# CircuitPython_Macro_Keyboard.net
KiCad netlist of a schematic drawn in EasyEDA
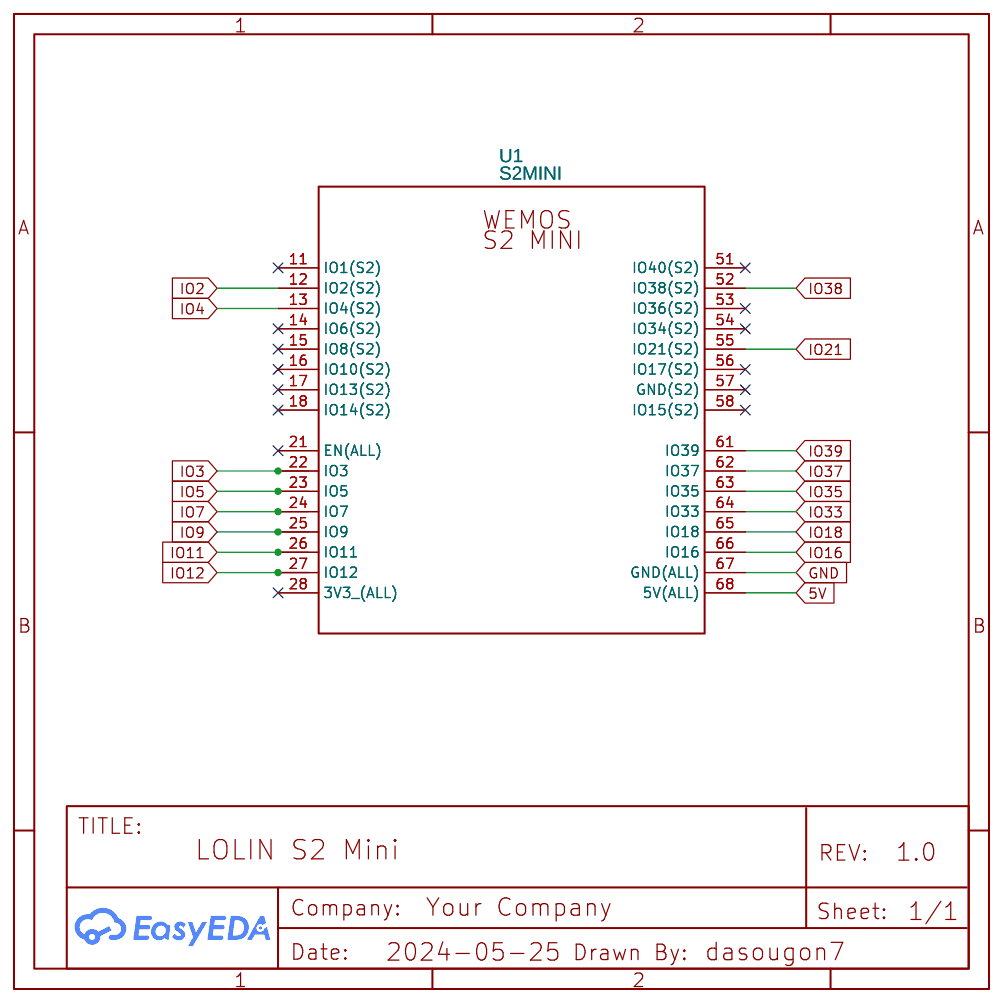
[diagram p0: LOLIN S2]
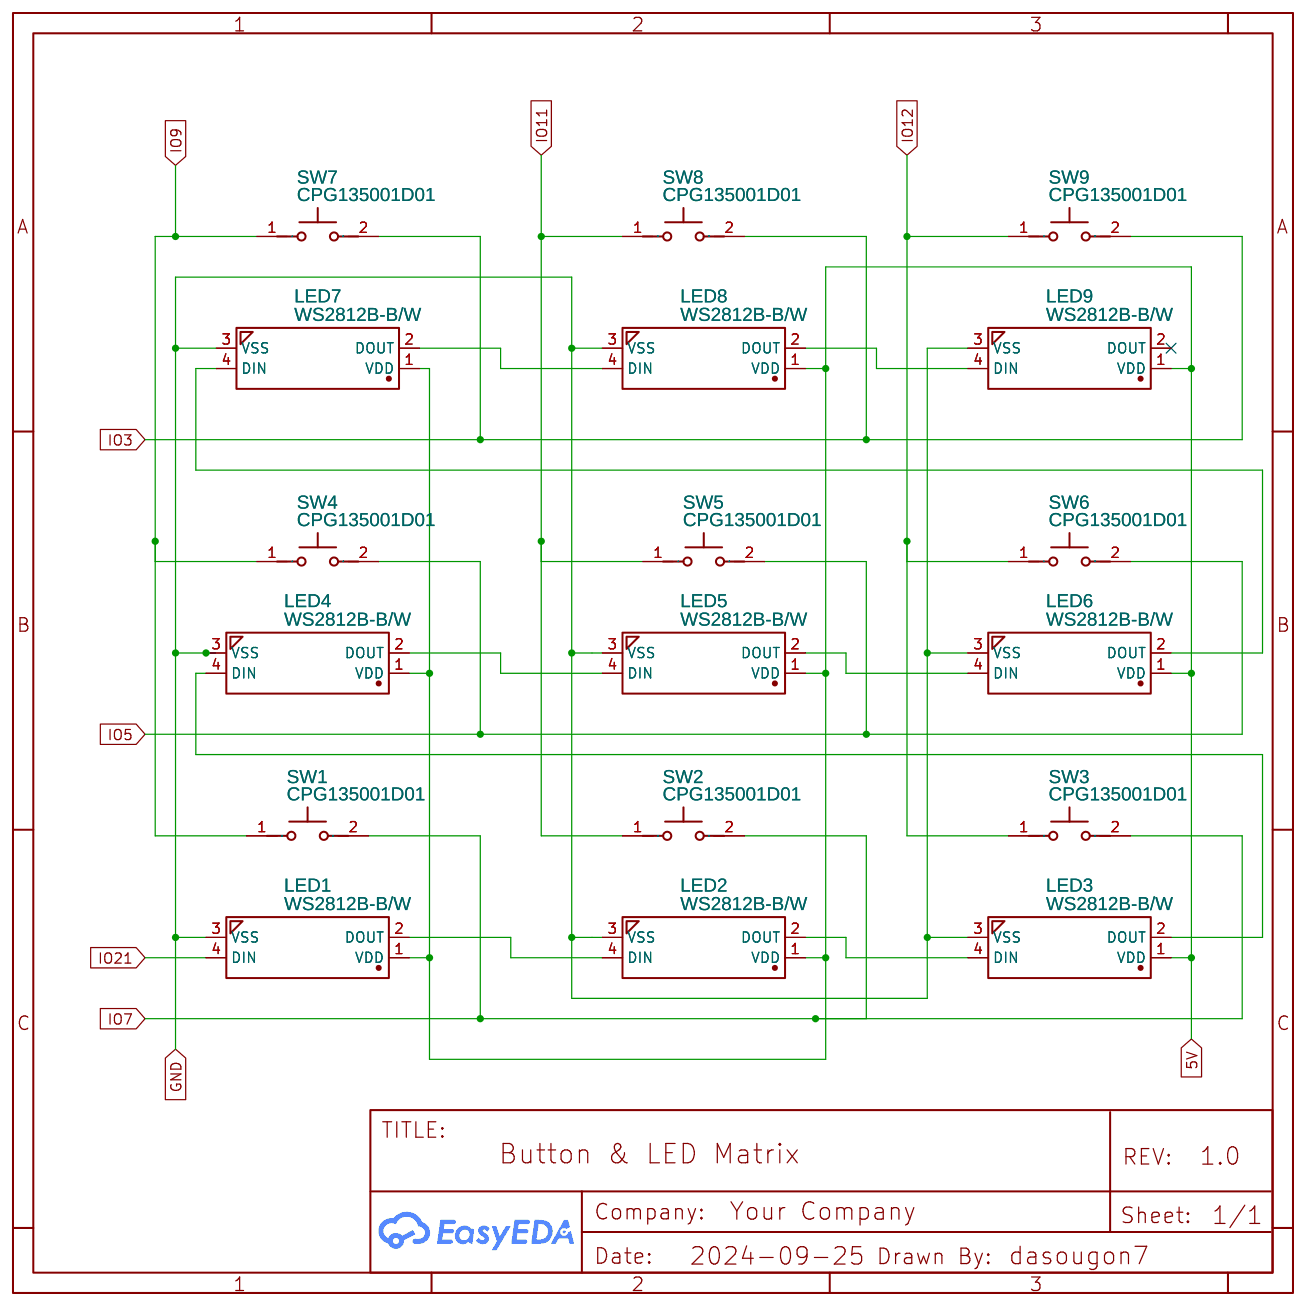
[diagram p1: Button Matrix]
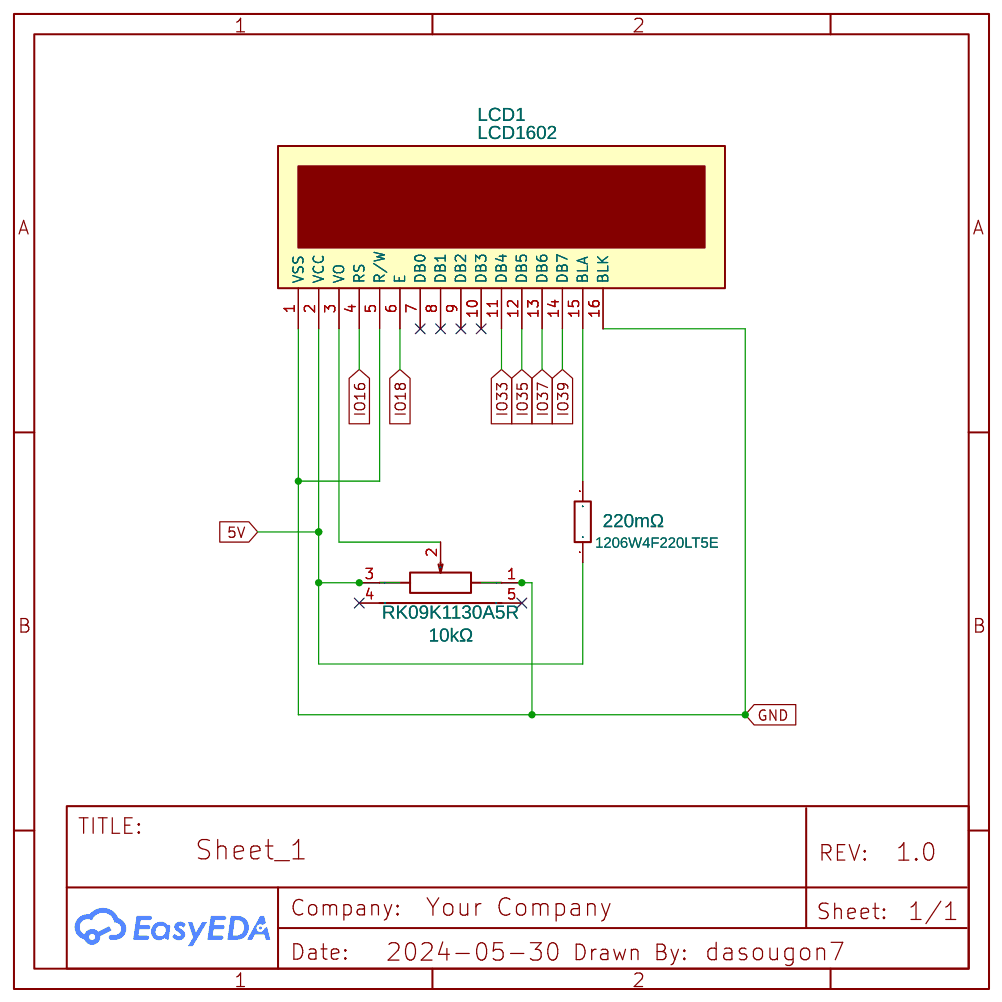
[diagram p2: LCD1602]
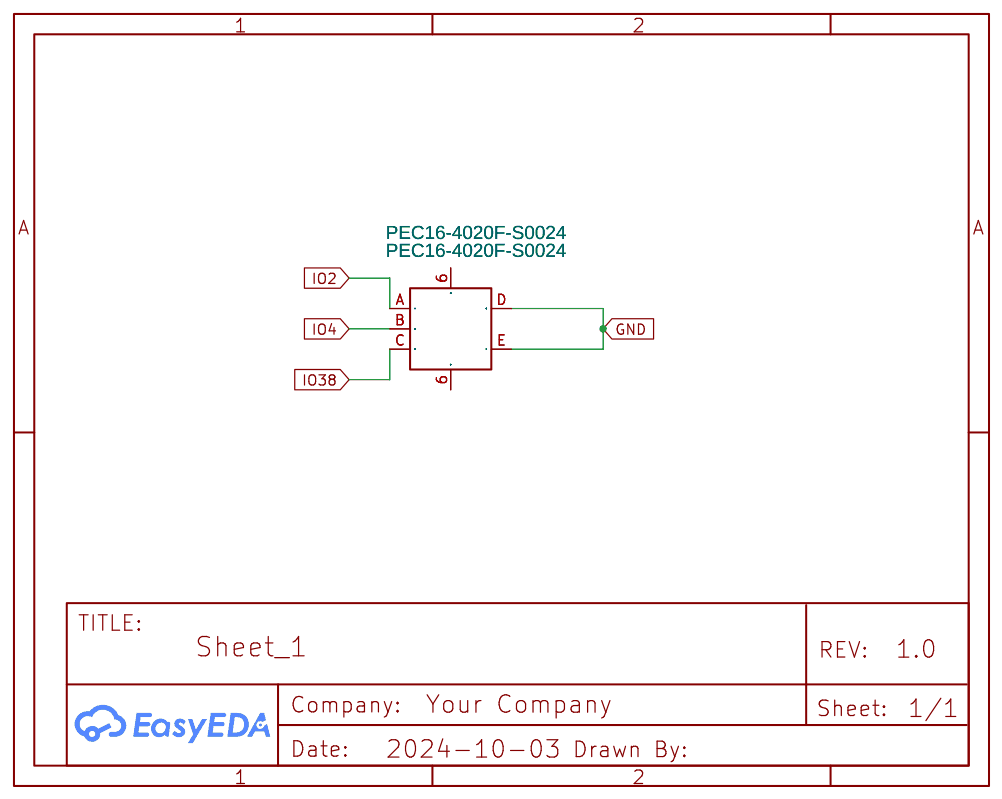
[diagram p3: Rotary Encoder]

(export (version "E")
  (design (tool "Eeschema 10.0.6"))
  (components
    (comp (ref "U1")
      (value "S2MINI")
      (fields (field (name "Manufacturer Part") "Wemos") (field (name "Manufacturer") "WEMOS"))
      (libsource (lib "") (part "S2MINI"))
    )
    (comp (ref "LED1")
      (value "WS2812B-B/W")
      (fields (field (name "Manufacturer Part") "WS2812B-B/T") (field (name "Manufacturer") "worldsemi"))
      (libsource (lib "") (part "WS2812B-B/W"))
    )
    (comp (ref "LED2")
      (value "WS2812B-B/W")
      (fields (field (name "Manufacturer Part") "WS2812B-B/T") (field (name "Manufacturer") "worldsemi"))
      (libsource (lib "") (part "WS2812B-B/W"))
    )
    (comp (ref "LED3")
      (value "WS2812B-B/W")
      (fields (field (name "Manufacturer Part") "WS2812B-B/T") (field (name "Manufacturer") "worldsemi"))
      (libsource (lib "") (part "WS2812B-B/W"))
    )
    (comp (ref "LED4")
      (value "WS2812B-B/W")
      (fields (field (name "Manufacturer Part") "WS2812B-B/T") (field (name "Manufacturer") "worldsemi"))
      (libsource (lib "") (part "WS2812B-B/W"))
    )
    (comp (ref "LED5")
      (value "WS2812B-B/W")
      (fields (field (name "Manufacturer Part") "WS2812B-B/T") (field (name "Manufacturer") "worldsemi"))
      (libsource (lib "") (part "WS2812B-B/W"))
    )
    (comp (ref "LED6")
      (value "WS2812B-B/W")
      (fields (field (name "Manufacturer Part") "WS2812B-B/T") (field (name "Manufacturer") "worldsemi"))
      (libsource (lib "") (part "WS2812B-B/W"))
    )
    (comp (ref "LED7")
      (value "WS2812B-B/W")
      (fields (field (name "Manufacturer Part") "WS2812B-B/T") (field (name "Manufacturer") "worldsemi"))
      (libsource (lib "") (part "WS2812B-B/W"))
    )
    (comp (ref "LED8")
      (value "WS2812B-B/W")
      (fields (field (name "Manufacturer Part") "WS2812B-B/T") (field (name "Manufacturer") "worldsemi"))
      (libsource (lib "") (part "WS2812B-B/W"))
    )
    (comp (ref "LED9")
      (value "WS2812B-B/W")
      (fields (field (name "Manufacturer Part") "WS2812B-B/T") (field (name "Manufacturer") "worldsemi"))
      (libsource (lib "") (part "WS2812B-B/W"))
    )
    (comp (ref "SW1")
      (value "CPG135001D01")
      (fields (field (name "Manufacturer") "Kailh(凯华)"))
      (libsource (lib "") (part "CPG135001D01"))
    )
    (comp (ref "SW2")
      (value "CPG135001D01")
      (fields (field (name "Manufacturer") "Kailh(凯华)"))
      (libsource (lib "") (part "CPG135001D01"))
    )
    (comp (ref "SW3")
      (value "CPG135001D01")
      (fields (field (name "Manufacturer") "Kailh(凯华)"))
      (libsource (lib "") (part "CPG135001D01"))
    )
    (comp (ref "SW4")
      (value "CPG135001D01")
      (fields (field (name "Manufacturer") "Kailh(凯华)"))
      (libsource (lib "") (part "CPG135001D01"))
    )
    (comp (ref "SW5")
      (value "CPG135001D01")
      (fields (field (name "Manufacturer") "Kailh(凯华)"))
      (libsource (lib "") (part "CPG135001D01"))
    )
    (comp (ref "SW6")
      (value "CPG135001D01")
      (fields (field (name "Manufacturer") "Kailh(凯华)"))
      (libsource (lib "") (part "CPG135001D01"))
    )
    (comp (ref "SW7")
      (value "CPG135001D01")
      (fields (field (name "Manufacturer") "Kailh(凯华)"))
      (libsource (lib "") (part "CPG135001D01"))
    )
    (comp (ref "SW8")
      (value "CPG135001D01")
      (fields (field (name "Manufacturer") "Kailh(凯华)"))
      (libsource (lib "") (part "CPG135001D01"))
    )
    (comp (ref "SW9")
      (value "CPG135001D01")
      (fields (field (name "Manufacturer") "Kailh(凯华)"))
      (libsource (lib "") (part "CPG135001D01"))
    )
    (comp (ref "1206W4F220LT5E")
      (value "220mΩ")
      (fields
        (field (name "Manufacturer Part") "1206W4F220LT5E")
        (field (name "Manufacturer") "UNI-ROYAL(厚声)")
      )
      (libsource (lib "") (part "1206W4F220LT5E"))
    )
    (comp (ref "LCD1")
      (value "LCD1602")
      (fields (field (name "Manufacturer Part") "HS1602A-Y") (field (name "Manufacturer") "HS(汉昇)"))
      (libsource (lib "") (part "LCD1602"))
    )
    (comp (ref "RK09K1130A5R")
      (value "10kΩ")
      (fields
        (field (name "Manufacturer Part") "RK09K1130A5R")
        (field (name "Manufacturer") "ALPSALPINE(阿尔卑斯阿尔派)")
      )
      (libsource (lib "") (part "RK09K1130A5R"))
    )
    (comp (ref "PEC16-4020F-S0024")
      (value "PEC16-4020F-S0024")
      (fields (field (name "Manufacturer") "BOURNS"))
      (libsource (lib "") (part "PEC16-4020F-S0024"))
    )
  )
  (nets
    (net (code "1") (name "5V") (class "Default")
      (node (ref "1206W4F220LT5E") (pin "1") (pinfunction "1_1") (pintype "input"))
      (node (ref "LCD1") (pin "2") (pinfunction "VCC_2") (pintype "unspecified"))
      (node (ref "LED1") (pin "1") (pinfunction "VDD_1") (pintype "unspecified"))
      (node (ref "LED2") (pin "1") (pinfunction "VDD_1") (pintype "unspecified"))
      (node (ref "LED3") (pin "1") (pinfunction "VDD_1") (pintype "unspecified"))
      (node (ref "LED4") (pin "1") (pinfunction "VDD_1") (pintype "unspecified"))
      (node (ref "LED5") (pin "1") (pinfunction "VDD_1") (pintype "unspecified"))
      (node (ref "LED6") (pin "1") (pinfunction "VDD_1") (pintype "unspecified"))
      (node (ref "LED7") (pin "1") (pinfunction "VDD_1") (pintype "unspecified"))
      (node (ref "LED8") (pin "1") (pinfunction "VDD_1") (pintype "unspecified"))
      (node (ref "LED9") (pin "1") (pinfunction "VDD_1") (pintype "unspecified"))
      (node (ref "RK09K1130A5R") (pin "3") (pinfunction "3_3") (pintype "unspecified"))
      (node (ref "U1") (pin "68") (pinfunction "5V(ALL)_68") (pintype "passive"))
    )
    (net (code "2") (name "GND") (class "Default")
      (node (ref "LCD1") (pin "1") (pinfunction "VSS_1") (pintype "unspecified"))
      (node (ref "LCD1") (pin "16") (pinfunction "BLK_16") (pintype "unspecified"))
      (node (ref "LCD1") (pin "5") (pinfunction "R/W_5") (pintype "unspecified"))
      (node (ref "LED1") (pin "3") (pinfunction "VSS_3") (pintype "unspecified"))
      (node (ref "LED2") (pin "3") (pinfunction "VSS_3") (pintype "unspecified"))
      (node (ref "LED3") (pin "3") (pinfunction "VSS_3") (pintype "unspecified"))
      (node (ref "LED4") (pin "3") (pinfunction "VSS_3") (pintype "unspecified"))
      (node (ref "LED5") (pin "3") (pinfunction "VSS_3") (pintype "unspecified"))
      (node (ref "LED6") (pin "3") (pinfunction "VSS_3") (pintype "unspecified"))
      (node (ref "LED7") (pin "3") (pinfunction "VSS_3") (pintype "unspecified"))
      (node (ref "LED8") (pin "3") (pinfunction "VSS_3") (pintype "unspecified"))
      (node (ref "LED9") (pin "3") (pinfunction "VSS_3") (pintype "unspecified"))
      (node (ref "PEC16-4020F-S0024") (pin "D") (pinfunction "D_D") (pintype "unspecified"))
      (node (ref "PEC16-4020F-S0024") (pin "E") (pinfunction "E_E") (pintype "unspecified"))
      (node (ref "RK09K1130A5R") (pin "1") (pinfunction "1_1") (pintype "unspecified"))
      (node (ref "U1") (pin "67") (pinfunction "GND(ALL)_67") (pintype "passive"))
    )
    (net (code "3") (name "IO2") (class "Default")
      (node (ref "PEC16-4020F-S0024") (pin "A") (pinfunction "A_A") (pintype "unspecified"))
      (node (ref "U1") (pin "12") (pinfunction "IO2(S2)_12") (pintype "bidirectional"))
    )
    (net (code "4") (name "IO3") (class "Default")
      (node (ref "SW7") (pin "2") (pinfunction "2_2") (pintype "unspecified"))
      (node (ref "SW8") (pin "2") (pinfunction "2_2") (pintype "unspecified"))
      (node (ref "SW9") (pin "2") (pinfunction "2_2") (pintype "unspecified"))
      (node (ref "U1") (pin "22") (pinfunction "IO3_22") (pintype "bidirectional"))
    )
    (net (code "5") (name "IO4") (class "Default")
      (node (ref "PEC16-4020F-S0024") (pin "B") (pinfunction "B_B") (pintype "unspecified"))
      (node (ref "U1") (pin "13") (pinfunction "IO4(S2)_13") (pintype "bidirectional"))
    )
    (net (code "6") (name "IO5") (class "Default")
      (node (ref "SW4") (pin "2") (pinfunction "2_2") (pintype "unspecified"))
      (node (ref "SW5") (pin "2") (pinfunction "2_2") (pintype "unspecified"))
      (node (ref "SW6") (pin "2") (pinfunction "2_2") (pintype "unspecified"))
      (node (ref "U1") (pin "23") (pinfunction "IO5_23") (pintype "bidirectional"))
    )
    (net (code "7") (name "IO7") (class "Default")
      (node (ref "SW1") (pin "2") (pinfunction "2_2") (pintype "unspecified"))
      (node (ref "SW2") (pin "2") (pinfunction "2_2") (pintype "unspecified"))
      (node (ref "SW3") (pin "2") (pinfunction "2_2") (pintype "unspecified"))
      (node (ref "U1") (pin "24") (pinfunction "IO7_24") (pintype "bidirectional"))
    )
    (net (code "8") (name "IO9") (class "Default")
      (node (ref "SW1") (pin "1") (pinfunction "1_1") (pintype "unspecified"))
      (node (ref "SW4") (pin "1") (pinfunction "1_1") (pintype "unspecified"))
      (node (ref "SW7") (pin "1") (pinfunction "1_1") (pintype "unspecified"))
      (node (ref "U1") (pin "25") (pinfunction "IO9_25") (pintype "bidirectional"))
    )
    (net (code "9") (name "IO11") (class "Default")
      (node (ref "SW2") (pin "1") (pinfunction "1_1") (pintype "unspecified"))
      (node (ref "SW5") (pin "1") (pinfunction "1_1") (pintype "unspecified"))
      (node (ref "SW8") (pin "1") (pinfunction "1_1") (pintype "unspecified"))
      (node (ref "U1") (pin "26") (pinfunction "IO11_26") (pintype "bidirectional"))
    )
    (net (code "10") (name "IO12") (class "Default")
      (node (ref "SW3") (pin "1") (pinfunction "1_1") (pintype "unspecified"))
      (node (ref "SW6") (pin "1") (pinfunction "1_1") (pintype "unspecified"))
      (node (ref "SW9") (pin "1") (pinfunction "1_1") (pintype "unspecified"))
      (node (ref "U1") (pin "27") (pinfunction "IO12_27") (pintype "bidirectional"))
    )
    (net (code "11") (name "IO16") (class "Default")
      (node (ref "LCD1") (pin "4") (pinfunction "RS_4") (pintype "unspecified"))
      (node (ref "U1") (pin "66") (pinfunction "IO16_66") (pintype "passive"))
    )
    (net (code "12") (name "IO18") (class "Default")
      (node (ref "LCD1") (pin "6") (pinfunction "E_6") (pintype "unspecified"))
      (node (ref "U1") (pin "65") (pinfunction "IO18_65") (pintype "passive"))
    )
    (net (code "13") (name "IO21") (class "Default")
      (node (ref "LED1") (pin "4") (pinfunction "DIN_4") (pintype "unspecified"))
      (node (ref "U1") (pin "55") (pinfunction "IO21(S2)_55") (pintype "passive"))
    )
    (net (code "14") (name "IO33") (class "Default")
      (node (ref "LCD1") (pin "11") (pinfunction "DB4_11") (pintype "unspecified"))
      (node (ref "U1") (pin "64") (pinfunction "IO33_64") (pintype "passive"))
    )
    (net (code "15") (name "IO35") (class "Default")
      (node (ref "LCD1") (pin "12") (pinfunction "DB5_12") (pintype "unspecified"))
      (node (ref "U1") (pin "63") (pinfunction "IO35_63") (pintype "passive"))
    )
    (net (code "16") (name "IO37") (class "Default")
      (node (ref "LCD1") (pin "13") (pinfunction "DB6_13") (pintype "unspecified"))
      (node (ref "U1") (pin "62") (pinfunction "IO37_62") (pintype "passive"))
    )
    (net (code "17") (name "IO38") (class "Default")
      (node (ref "PEC16-4020F-S0024") (pin "C") (pinfunction "C_C") (pintype "unspecified"))
      (node (ref "U1") (pin "52") (pinfunction "IO38(S2)_52") (pintype "passive"))
    )
    (net (code "18") (name "IO39") (class "Default")
      (node (ref "LCD1") (pin "14") (pinfunction "DB7_14") (pintype "unspecified"))
      (node (ref "U1") (pin "61") (pinfunction "IO39_61") (pintype "passive"))
    )
    (net (code "19") (name "Net-(LCD1-BLA)") (class "Default")
      (node (ref "1206W4F220LT5E") (pin "2") (pinfunction "2_2") (pintype "input"))
      (node (ref "LCD1") (pin "15") (pinfunction "BLA_15") (pintype "unspecified"))
    )
    (net (code "20") (name "Net-(LCD1-VO)") (class "Default")
      (node (ref "LCD1") (pin "3") (pinfunction "VO_3") (pintype "unspecified"))
      (node (ref "RK09K1130A5R") (pin "2") (pinfunction "2_2") (pintype "unspecified"))
    )
    (net (code "21") (name "Net-(LED1-DOUT)") (class "Default")
      (node (ref "LED1") (pin "2") (pinfunction "DOUT_2") (pintype "unspecified"))
      (node (ref "LED2") (pin "4") (pinfunction "DIN_4") (pintype "unspecified"))
    )
    (net (code "22") (name "Net-(LED2-DOUT)") (class "Default")
      (node (ref "LED2") (pin "2") (pinfunction "DOUT_2") (pintype "unspecified"))
      (node (ref "LED3") (pin "4") (pinfunction "DIN_4") (pintype "unspecified"))
    )
    (net (code "23") (name "Net-(LED3-DOUT)") (class "Default")
      (node (ref "LED3") (pin "2") (pinfunction "DOUT_2") (pintype "unspecified"))
      (node (ref "LED4") (pin "4") (pinfunction "DIN_4") (pintype "unspecified"))
    )
    (net (code "24") (name "Net-(LED4-DOUT)") (class "Default")
      (node (ref "LED4") (pin "2") (pinfunction "DOUT_2") (pintype "unspecified"))
      (node (ref "LED5") (pin "4") (pinfunction "DIN_4") (pintype "unspecified"))
    )
    (net (code "25") (name "Net-(LED5-DOUT)") (class "Default")
      (node (ref "LED5") (pin "2") (pinfunction "DOUT_2") (pintype "unspecified"))
      (node (ref "LED6") (pin "4") (pinfunction "DIN_4") (pintype "unspecified"))
    )
    (net (code "26") (name "Net-(LED6-DOUT)") (class "Default")
      (node (ref "LED6") (pin "2") (pinfunction "DOUT_2") (pintype "unspecified"))
      (node (ref "LED7") (pin "4") (pinfunction "DIN_4") (pintype "unspecified"))
    )
    (net (code "27") (name "Net-(LED7-DOUT)") (class "Default")
      (node (ref "LED7") (pin "2") (pinfunction "DOUT_2") (pintype "unspecified"))
      (node (ref "LED8") (pin "4") (pinfunction "DIN_4") (pintype "unspecified"))
    )
    (net (code "28") (name "Net-(LED8-DOUT)") (class "Default")
      (node (ref "LED8") (pin "2") (pinfunction "DOUT_2") (pintype "unspecified"))
      (node (ref "LED9") (pin "4") (pinfunction "DIN_4") (pintype "unspecified"))
    )
    (net (code "29") (name "unconnected-(LCD1-DB0-Pad7)") (class "Default")
      (node (ref "LCD1") (pin "7") (pinfunction "DB0_7") (pintype "unspecified+no_connect"))
    )
    (net (code "30") (name "unconnected-(LCD1-DB1-Pad8)") (class "Default")
      (node (ref "LCD1") (pin "8") (pinfunction "DB1_8") (pintype "unspecified+no_connect"))
    )
    (net (code "31") (name "unconnected-(LCD1-DB2-Pad9)") (class "Default")
      (node (ref "LCD1") (pin "9") (pinfunction "DB2_9") (pintype "unspecified+no_connect"))
    )
    (net (code "32") (name "unconnected-(LCD1-DB3-Pad10)") (class "Default")
      (node (ref "LCD1") (pin "10") (pinfunction "DB3_10") (pintype "unspecified+no_connect"))
    )
    (net (code "33") (name "unconnected-(LED9-DOUT-Pad2)") (class "Default")
      (node (ref "LED9") (pin "2") (pinfunction "DOUT_2") (pintype "unspecified+no_connect"))
    )
    (net (code "34") (name "unconnected-(PEC16-4020F-S0024-Pad6)") (class "Default")
      (node (ref "PEC16-4020F-S0024") (pin "6") (pinfunction "6_6") (pintype "unspecified"))
    )
    (net (code "35") (name "unconnected-(PEC16-4020F-S0024-Pad6)_1") (class "Default")
      (node (ref "PEC16-4020F-S0024") (pin "6") (pinfunction "6_6") (pintype "unspecified"))
    )
    (net (code "36") (name "unconnected-(RK09K1130A5R-EH-Pad4)") (class "Default")
      (node (ref "RK09K1130A5R") (pin "4") (pinfunction "EH_4") (pintype "unspecified+no_connect"))
    )
    (net (code "37") (name "unconnected-(RK09K1130A5R-EH-Pad5)") (class "Default")
      (node (ref "RK09K1130A5R") (pin "5") (pinfunction "EH_5") (pintype "unspecified+no_connect"))
    )
    (net (code "38") (name "unconnected-(U1-3V3_(ALL)-Pad28)") (class "Default")
      (node (ref "U1") (pin "28") (pinfunction "3V3_(ALL)_28") (pintype "bidirectional+no_connect"))
    )
    (net (code "39") (name "unconnected-(U1-EN(ALL)-Pad21)") (class "Default")
      (node (ref "U1") (pin "21") (pinfunction "EN(ALL)_21") (pintype "bidirectional+no_connect"))
    )
    (net (code "40") (name "unconnected-(U1-GND(S2)-Pad57)") (class "Default")
      (node (ref "U1") (pin "57") (pinfunction "GND(S2)_57") (pintype "passive+no_connect"))
    )
    (net (code "41") (name "unconnected-(U1-IO1(S2)-Pad11)") (class "Default")
      (node (ref "U1") (pin "11") (pinfunction "IO1(S2)_11") (pintype "input+no_connect"))
    )
    (net (code "42") (name "unconnected-(U1-IO6(S2)-Pad14)") (class "Default")
      (node (ref "U1") (pin "14") (pinfunction "IO6(S2)_14") (pintype "bidirectional+no_connect"))
    )
    (net (code "43") (name "unconnected-(U1-IO8(S2)-Pad15)") (class "Default")
      (node (ref "U1") (pin "15") (pinfunction "IO8(S2)_15") (pintype "bidirectional+no_connect"))
    )
    (net (code "44") (name "unconnected-(U1-IO10(S2)-Pad16)") (class "Default")
      (node (ref "U1") (pin "16") (pinfunction "IO10(S2)_16") (pintype "bidirectional+no_connect"))
    )
    (net (code "45") (name "unconnected-(U1-IO13(S2)-Pad17)") (class "Default")
      (node (ref "U1") (pin "17") (pinfunction "IO13(S2)_17") (pintype "bidirectional+no_connect"))
    )
    (net (code "46") (name "unconnected-(U1-IO14(S2)-Pad18)") (class "Default")
      (node (ref "U1") (pin "18") (pinfunction "IO14(S2)_18") (pintype "bidirectional+no_connect"))
    )
    (net (code "47") (name "unconnected-(U1-IO15(S2)-Pad58)") (class "Default")
      (node (ref "U1") (pin "58") (pinfunction "IO15(S2)_58") (pintype "passive+no_connect"))
    )
    (net (code "48") (name "unconnected-(U1-IO17(S2)-Pad56)") (class "Default")
      (node (ref "U1") (pin "56") (pinfunction "IO17(S2)_56") (pintype "passive+no_connect"))
    )
    (net (code "49") (name "unconnected-(U1-IO34(S2)-Pad54)") (class "Default")
      (node (ref "U1") (pin "54") (pinfunction "IO34(S2)_54") (pintype "passive+no_connect"))
    )
    (net (code "50") (name "unconnected-(U1-IO36(S2)-Pad53)") (class "Default")
      (node (ref "U1") (pin "53") (pinfunction "IO36(S2)_53") (pintype "passive+no_connect"))
    )
    (net (code "51") (name "unconnected-(U1-IO40(S2)-Pad51)") (class "Default")
      (node (ref "U1") (pin "51") (pinfunction "IO40(S2)_51") (pintype "passive+no_connect"))
    )
  )
)
